# main.net
KiCad netlist of a schematic drawn in Altium Designer
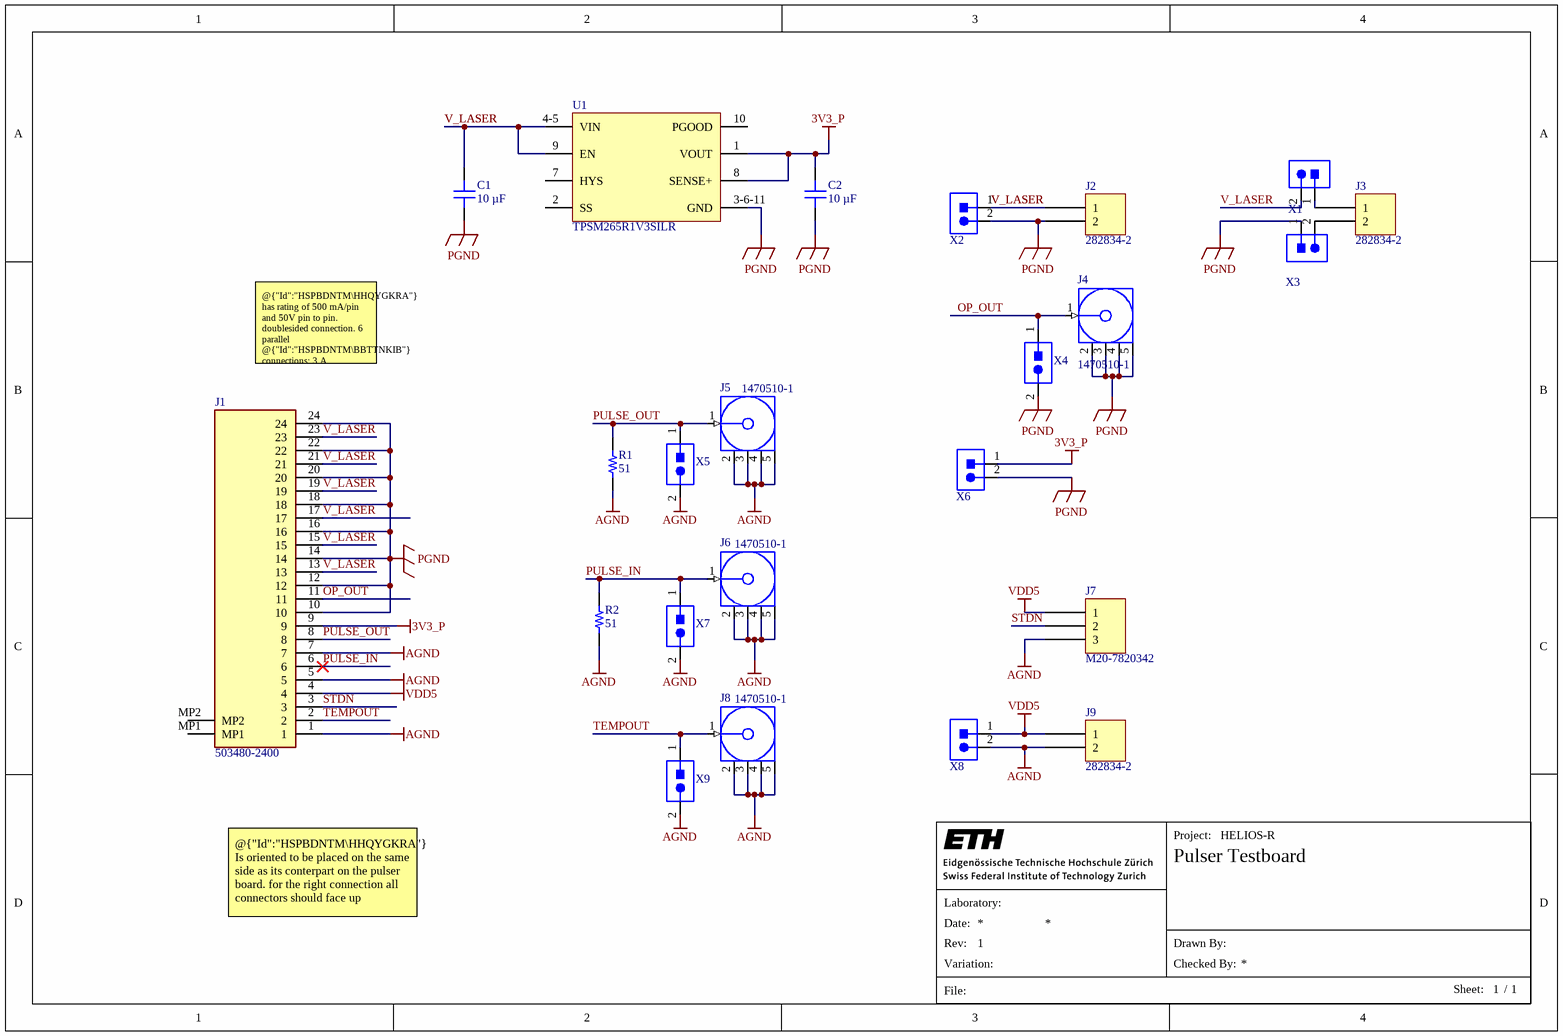
[diagram p0: main.SchDoc]

(export (version "E")
  (design (tool "Eeschema 10.0.6"))
  (components
    (comp (ref "C1")
      (value "10 µF")
      (footprint "CAP 1210_3225 - 1MM")
      (description "CAP CER 10UF 100V X7S 1210")
      (fields
        (field (name "PART NUMBER") "GRM32EC72A106ME05L")
        (field (name "MANUFACTURER") "Murata Electronics")
      )
      (libsource (lib "ld_pulser") (part "GRM32EC72A106ME05L"))
    )
    (comp (ref "C2")
      (value "10 µF")
      (footprint "CAP 1210_3225 - 1MM")
      (description "CAP CER 10UF 100V X7S 1210")
      (fields
        (field (name "PART NUMBER") "GRM32EC72A106ME05L")
        (field (name "MANUFACTURER") "Murata Electronics")
      )
      (libsource (lib "ld_pulser") (part "GRM32EC72A106ME05L"))
    )
    (comp (ref "J1")
      (value "503480-2400")
      (footprint "SamacSys:5034802400")
      (description "Connector")
      (fields (field (name "MOUSER PART NUMBER") "538-503480-2400"))
      (libsource (lib "*") (part "503480-2400"))
    )
    (comp (ref "J2")
      (value "282834-2")
      (footprint "TE 282834-2")
      (description "TERM BLK 2P SIDE ENT 2.54MM PCB")
      (fields (field (name "MANUFACTURER") "TE Connectivity AMP Connectors") (field (name "VOLTAGE") "150V"))
      (libsource (lib "clib") (part "2 Pin"))
    )
    (comp (ref "J3")
      (value "282834-2")
      (footprint "TE 282834-2")
      (description "TERM BLK 2P SIDE ENT 2.54MM PCB")
      (fields (field (name "MANUFACTURER") "TE Connectivity AMP Connectors") (field (name "VOLTAGE") "150V"))
      (libsource (lib "clib") (part "2 Pin"))
    )
    (comp (ref "J4")
      (value "1470510-1")
      (footprint "5-1814832-1")
      (description "SMA Connector Jack, Female Socket 50 Ohm Through Hole Solder")
      (fields (field (name "MANUFACTURER") "TE Connectivity"))
      (libsource (lib "ld_pulser") (part "CMP-00606-1"))
    )
    (comp (ref "J5")
      (value "1470510-1")
      (footprint "5-1814832-1")
      (description "SMA Connector Jack, Female Socket 50 Ohm Through Hole Solder")
      (fields (field (name "MANUFACTURER") "TE Connectivity"))
      (libsource (lib "ld_pulser") (part "CMP-00606-1"))
    )
    (comp (ref "J6")
      (value "1470510-1")
      (footprint "5-1814832-1")
      (description "SMA Connector Jack, Female Socket 50 Ohm Through Hole Solder")
      (fields (field (name "MANUFACTURER") "TE Connectivity"))
      (libsource (lib "ld_pulser") (part "CMP-00606-1"))
    )
    (comp (ref "J7")
      (value "M20-7820342")
      (footprint "HARWIN M20-7820345")
      (description "CONN RCPT 3POS 0.1 GOLD PCB")
      (fields (field (name "MANUFACTURER") "Harwin Inc."))
      (libsource (lib "clib") (part "3 Pin"))
    )
    (comp (ref "J8")
      (value "1470510-1")
      (footprint "5-1814832-1")
      (description "SMA Connector Jack, Female Socket 50 Ohm Through Hole Solder")
      (fields (field (name "MANUFACTURER") "TE Connectivity"))
      (libsource (lib "ld_pulser") (part "CMP-00606-1"))
    )
    (comp (ref "J9")
      (value "282834-2")
      (footprint "TE 282834-2")
      (description "TERM BLK 2P SIDE ENT 2.54MM PCB")
      (fields (field (name "MANUFACTURER") "TE Connectivity AMP Connectors") (field (name "VOLTAGE") "150V"))
      (libsource (lib "clib") (part "2 Pin"))
    )
    (comp (ref "R1")
      (value "51")
      (footprint "RES 0201_0603")
      (description "RES SMD 51 OHM 1% 1/20W 0201")
      (fields
        (field (name "MANUFACTURER") "Panasonic")
        (field (name "MANUFACTURER PART NUMBER") "ERJ1GNF51R0C")
      )
      (libsource (lib "ld_pulser") (part "ERJ-1GNF51R0C"))
    )
    (comp (ref "R2")
      (value "51")
      (footprint "RES 0201_0603")
      (description "RES SMD 51 OHM 1% 1/20W 0201")
      (fields
        (field (name "MANUFACTURER") "Panasonic")
        (field (name "MANUFACTURER PART NUMBER") "ERJ1GNF51R0C")
      )
      (libsource (lib "ld_pulser") (part "ERJ-1GNF51R0C"))
    )
    (comp (ref "U1")
      (value "TPSM265R1V3SILR")
      (footprint "FP-SIL0010C-MFG")
      (description "3-V TO 65-V INPUT, 100-MA, STEP-")
      (fields (field (name "MANUFACTURER") "Texas Instruments"))
      (libsource (lib "ld_pulser") (part "TPSM265R1V3SILR"))
    )
    (comp (ref "X1")
      (value "68000-102HLF")
      (footprint "68000-102HLF")
      (description "2 Positions Header, Unshrouded Connector 0.100\" (2.54mm) Through Hole Gold or Gold, GXT™")
      (fields (field (name "MANUFACTURER") "Amphenol FCI"))
      (libsource (lib "xdcr") (part "CMP-00100-3"))
    )
    (comp (ref "X2")
      (value "68000-102HLF")
      (footprint "68000-102HLF")
      (description "2 Positions Header, Unshrouded Connector 0.100\" (2.54mm) Through Hole Gold or Gold, GXT™")
      (fields (field (name "MANUFACTURER") "Amphenol FCI"))
      (libsource (lib "") (part "CMP-00100-3_1"))
    )
    (comp (ref "X3")
      (value "68000-102HLF")
      (footprint "68000-102HLF")
      (description "2 Positions Header, Unshrouded Connector 0.100\" (2.54mm) Through Hole Gold or Gold, GXT™")
      (fields (field (name "MANUFACTURER") "Amphenol FCI"))
      (libsource (lib "") (part "CMP-00100-3_2"))
    )
    (comp (ref "X4")
      (value "68000-102HLF")
      (footprint "68000-102HLF")
      (description "2 Positions Header, Unshrouded Connector 0.100\" (2.54mm) Through Hole Gold or Gold, GXT™")
      (fields (field (name "MANUFACTURER") "Amphenol FCI"))
      (libsource (lib "ld_pulser") (part "CMP-00100-3_1"))
    )
    (comp (ref "X5")
      (value "68000-102HLF")
      (footprint "68000-102HLF")
      (description "2 Positions Header, Unshrouded Connector 0.100\" (2.54mm) Through Hole Gold or Gold, GXT™")
      (fields (field (name "MANUFACTURER") "Amphenol FCI"))
      (libsource (lib "ld_pulser") (part "CMP-00100-3_1"))
    )
    (comp (ref "X6")
      (value "68000-102HLF")
      (footprint "68000-102HLF")
      (description "2 Positions Header, Unshrouded Connector 0.100\" (2.54mm) Through Hole Gold or Gold, GXT™")
      (fields (field (name "MANUFACTURER") "Amphenol FCI"))
      (libsource (lib "") (part "CMP-00100-3_1"))
    )
    (comp (ref "X7")
      (value "68000-102HLF")
      (footprint "68000-102HLF")
      (description "2 Positions Header, Unshrouded Connector 0.100\" (2.54mm) Through Hole Gold or Gold, GXT™")
      (fields (field (name "MANUFACTURER") "Amphenol FCI"))
      (libsource (lib "ld_pulser") (part "CMP-00100-3_1"))
    )
    (comp (ref "X8")
      (value "68000-102HLF")
      (footprint "68000-102HLF")
      (description "2 Positions Header, Unshrouded Connector 0.100\" (2.54mm) Through Hole Gold or Gold, GXT™")
      (fields (field (name "MANUFACTURER") "Amphenol FCI"))
      (libsource (lib "") (part "CMP-00100-3_1"))
    )
    (comp (ref "X9")
      (value "68000-102HLF")
      (footprint "68000-102HLF")
      (description "2 Positions Header, Unshrouded Connector 0.100\" (2.54mm) Through Hole Gold or Gold, GXT™")
      (fields (field (name "MANUFACTURER") "Amphenol FCI"))
      (libsource (lib "ld_pulser") (part "CMP-00100-3_1"))
    )
  )
  (nets
    (net (code "1") (name "/OP_OUT") (class "Default")
      (node (ref "J1") (pin "11") (pinfunction "11_11") (pintype "passive"))
      (node (ref "J4") (pin "1") (pinfunction "Signal_1") (pintype "input"))
      (node (ref "X4") (pin "1") (pinfunction "1_1") (pintype "passive"))
    )
    (net (code "2") (name "/PULSE_IN") (class "Default")
      (node (ref "J1") (pin "6") (pinfunction "6_6") (pintype "passive"))
      (node (ref "J6") (pin "1") (pinfunction "Signal_1") (pintype "input"))
      (node (ref "R2") (pin "2") (pinfunction "2_2") (pintype "passive"))
      (node (ref "X7") (pin "1") (pinfunction "1_1") (pintype "passive"))
    )
    (net (code "3") (name "/PULSE_OUT") (class "Default")
      (node (ref "J1") (pin "8") (pinfunction "8_8") (pintype "passive"))
      (node (ref "J5") (pin "1") (pinfunction "Signal_1") (pintype "input"))
      (node (ref "R1") (pin "2") (pinfunction "2_2") (pintype "passive"))
      (node (ref "X5") (pin "1") (pinfunction "1_1") (pintype "passive"))
    )
    (net (code "4") (name "/STDN") (class "Default")
      (node (ref "J1") (pin "3") (pinfunction "3_3") (pintype "passive"))
      (node (ref "J7") (pin "2") (pinfunction "2_2") (pintype "passive"))
    )
    (net (code "5") (name "/TEMPOUT") (class "Default")
      (node (ref "J1") (pin "2") (pinfunction "2_2") (pintype "passive"))
      (node (ref "J8") (pin "1") (pinfunction "Signal_1") (pintype "input"))
      (node (ref "X9") (pin "1") (pinfunction "1_1") (pintype "passive"))
    )
    (net (code "6") (name "/V_LASER") (class "Default")
      (node (ref "C1") (pin "2") (pinfunction "2_2") (pintype "passive"))
      (node (ref "J1") (pin "13") (pinfunction "13_13") (pintype "passive"))
      (node (ref "J1") (pin "15") (pinfunction "15_15") (pintype "passive"))
      (node (ref "J1") (pin "17") (pinfunction "17_17") (pintype "passive"))
      (node (ref "J1") (pin "19") (pinfunction "19_19") (pintype "passive"))
      (node (ref "J1") (pin "21") (pinfunction "21_21") (pintype "passive"))
      (node (ref "J1") (pin "23") (pinfunction "23_23") (pintype "passive"))
      (node (ref "J2") (pin "1") (pinfunction "1_1") (pintype "passive"))
      (node (ref "U1") (pin "4-5") (pinfunction "VIN_4-5") (pintype "power_in"))
      (node (ref "U1") (pin "9") (pinfunction "EN_9") (pintype "passive"))
      (node (ref "X1") (pin "2") (pinfunction "2_2") (pintype "passive"))
      (node (ref "X2") (pin "1") (pinfunction "1_1") (pintype "passive"))
    )
    (net (code "7") (name "3V3_P") (class "Default")
      (node (ref "C2") (pin "2") (pinfunction "2_2") (pintype "passive"))
      (node (ref "J1") (pin "9") (pinfunction "9_9") (pintype "passive"))
      (node (ref "U1") (pin "1") (pinfunction "VOUT_1") (pintype "passive"))
      (node (ref "U1") (pin "8") (pinfunction "SENSE+_8") (pintype "power_in"))
      (node (ref "X6") (pin "1") (pinfunction "1_1") (pintype "passive"))
    )
    (net (code "8") (name "AGND") (class "Default")
      (node (ref "J1") (pin "1") (pinfunction "1_1") (pintype "passive"))
      (node (ref "J1") (pin "5") (pinfunction "5_5") (pintype "passive"))
      (node (ref "J1") (pin "7") (pinfunction "7_7") (pintype "passive"))
      (node (ref "J5") (pin "2") (pinfunction "GND_2") (pintype "power_in"))
      (node (ref "J5") (pin "3") (pinfunction "GND_3") (pintype "power_in"))
      (node (ref "J5") (pin "4") (pinfunction "GND_4") (pintype "power_in"))
      (node (ref "J5") (pin "5") (pinfunction "GND_5") (pintype "power_in"))
      (node (ref "J6") (pin "2") (pinfunction "GND_2") (pintype "power_in"))
      (node (ref "J6") (pin "3") (pinfunction "GND_3") (pintype "power_in"))
      (node (ref "J6") (pin "4") (pinfunction "GND_4") (pintype "power_in"))
      (node (ref "J6") (pin "5") (pinfunction "GND_5") (pintype "power_in"))
      (node (ref "J7") (pin "3") (pinfunction "3_3") (pintype "passive"))
      (node (ref "J8") (pin "2") (pinfunction "GND_2") (pintype "power_in"))
      (node (ref "J8") (pin "3") (pinfunction "GND_3") (pintype "power_in"))
      (node (ref "J8") (pin "4") (pinfunction "GND_4") (pintype "power_in"))
      (node (ref "J8") (pin "5") (pinfunction "GND_5") (pintype "power_in"))
      (node (ref "J9") (pin "2") (pinfunction "2_2") (pintype "passive"))
      (node (ref "R1") (pin "1") (pinfunction "1_1") (pintype "passive"))
      (node (ref "R2") (pin "1") (pinfunction "1_1") (pintype "passive"))
      (node (ref "X5") (pin "2") (pinfunction "2_2") (pintype "passive"))
      (node (ref "X7") (pin "2") (pinfunction "2_2") (pintype "passive"))
      (node (ref "X8") (pin "2") (pinfunction "2_2") (pintype "passive"))
      (node (ref "X9") (pin "2") (pinfunction "2_2") (pintype "passive"))
    )
    (net (code "9") (name "Net-(J3-Pad1)") (class "Default")
      (node (ref "J3") (pin "1") (pinfunction "1_1") (pintype "passive"))
      (node (ref "X1") (pin "1") (pinfunction "1_1") (pintype "passive"))
    )
    (net (code "10") (name "Net-(J3-Pad2)") (class "Default")
      (node (ref "J3") (pin "2") (pinfunction "2_2") (pintype "passive"))
      (node (ref "X3") (pin "2") (pinfunction "2_2") (pintype "passive"))
    )
    (net (code "11") (name "PGND") (class "Default")
      (node (ref "C1") (pin "1") (pinfunction "1_1") (pintype "passive"))
      (node (ref "C2") (pin "1") (pinfunction "1_1") (pintype "passive"))
      (node (ref "J1") (pin "10") (pinfunction "10_10") (pintype "passive"))
      (node (ref "J1") (pin "12") (pinfunction "12_12") (pintype "passive"))
      (node (ref "J1") (pin "14") (pinfunction "14_14") (pintype "passive"))
      (node (ref "J1") (pin "16") (pinfunction "16_16") (pintype "passive"))
      (node (ref "J1") (pin "18") (pinfunction "18_18") (pintype "passive"))
      (node (ref "J1") (pin "20") (pinfunction "20_20") (pintype "passive"))
      (node (ref "J1") (pin "22") (pinfunction "22_22") (pintype "passive"))
      (node (ref "J1") (pin "24") (pinfunction "24_24") (pintype "passive"))
      (node (ref "J2") (pin "2") (pinfunction "2_2") (pintype "passive"))
      (node (ref "J4") (pin "2") (pinfunction "GND_2") (pintype "power_in"))
      (node (ref "J4") (pin "3") (pinfunction "GND_3") (pintype "power_in"))
      (node (ref "J4") (pin "4") (pinfunction "GND_4") (pintype "power_in"))
      (node (ref "J4") (pin "5") (pinfunction "GND_5") (pintype "power_in"))
      (node (ref "U1") (pin "3-6-11") (pinfunction "GND_3-6-11") (pintype "power_in"))
      (node (ref "X2") (pin "2") (pinfunction "2_2") (pintype "passive"))
      (node (ref "X3") (pin "1") (pinfunction "1_1") (pintype "passive"))
      (node (ref "X4") (pin "2") (pinfunction "2_2") (pintype "passive"))
      (node (ref "X6") (pin "2") (pinfunction "2_2") (pintype "passive"))
    )
    (net (code "12") (name "VDD5") (class "Default")
      (node (ref "J1") (pin "4") (pinfunction "4_4") (pintype "passive"))
      (node (ref "J7") (pin "1") (pinfunction "1_1") (pintype "passive"))
      (node (ref "J9") (pin "1") (pinfunction "1_1") (pintype "passive"))
      (node (ref "X8") (pin "1") (pinfunction "1_1") (pintype "passive"))
    )
    (net (code "13") (name "unconnected-(J1-PadMP1)") (class "Default")
      (node (ref "J1") (pin "MP1") (pinfunction "MP1_MP1") (pintype "passive"))
    )
    (net (code "14") (name "unconnected-(J1-PadMP2)") (class "Default")
      (node (ref "J1") (pin "MP2") (pinfunction "MP2_MP2") (pintype "passive"))
    )
    (net (code "15") (name "unconnected-(U1-HYS-Pad7)") (class "Default")
      (node (ref "U1") (pin "7") (pinfunction "HYS_7") (pintype "power_in"))
    )
    (net (code "16") (name "unconnected-(U1-PGOOD-Pad10)") (class "Default")
      (node (ref "U1") (pin "10") (pinfunction "PGOOD_10") (pintype "passive"))
    )
    (net (code "17") (name "unconnected-(U1-SS-Pad2)") (class "Default")
      (node (ref "U1") (pin "2") (pinfunction "SS_2") (pintype "passive"))
    )
  )
)
